# pre.net
KiCad netlist of a schematic drawn in EAGLE
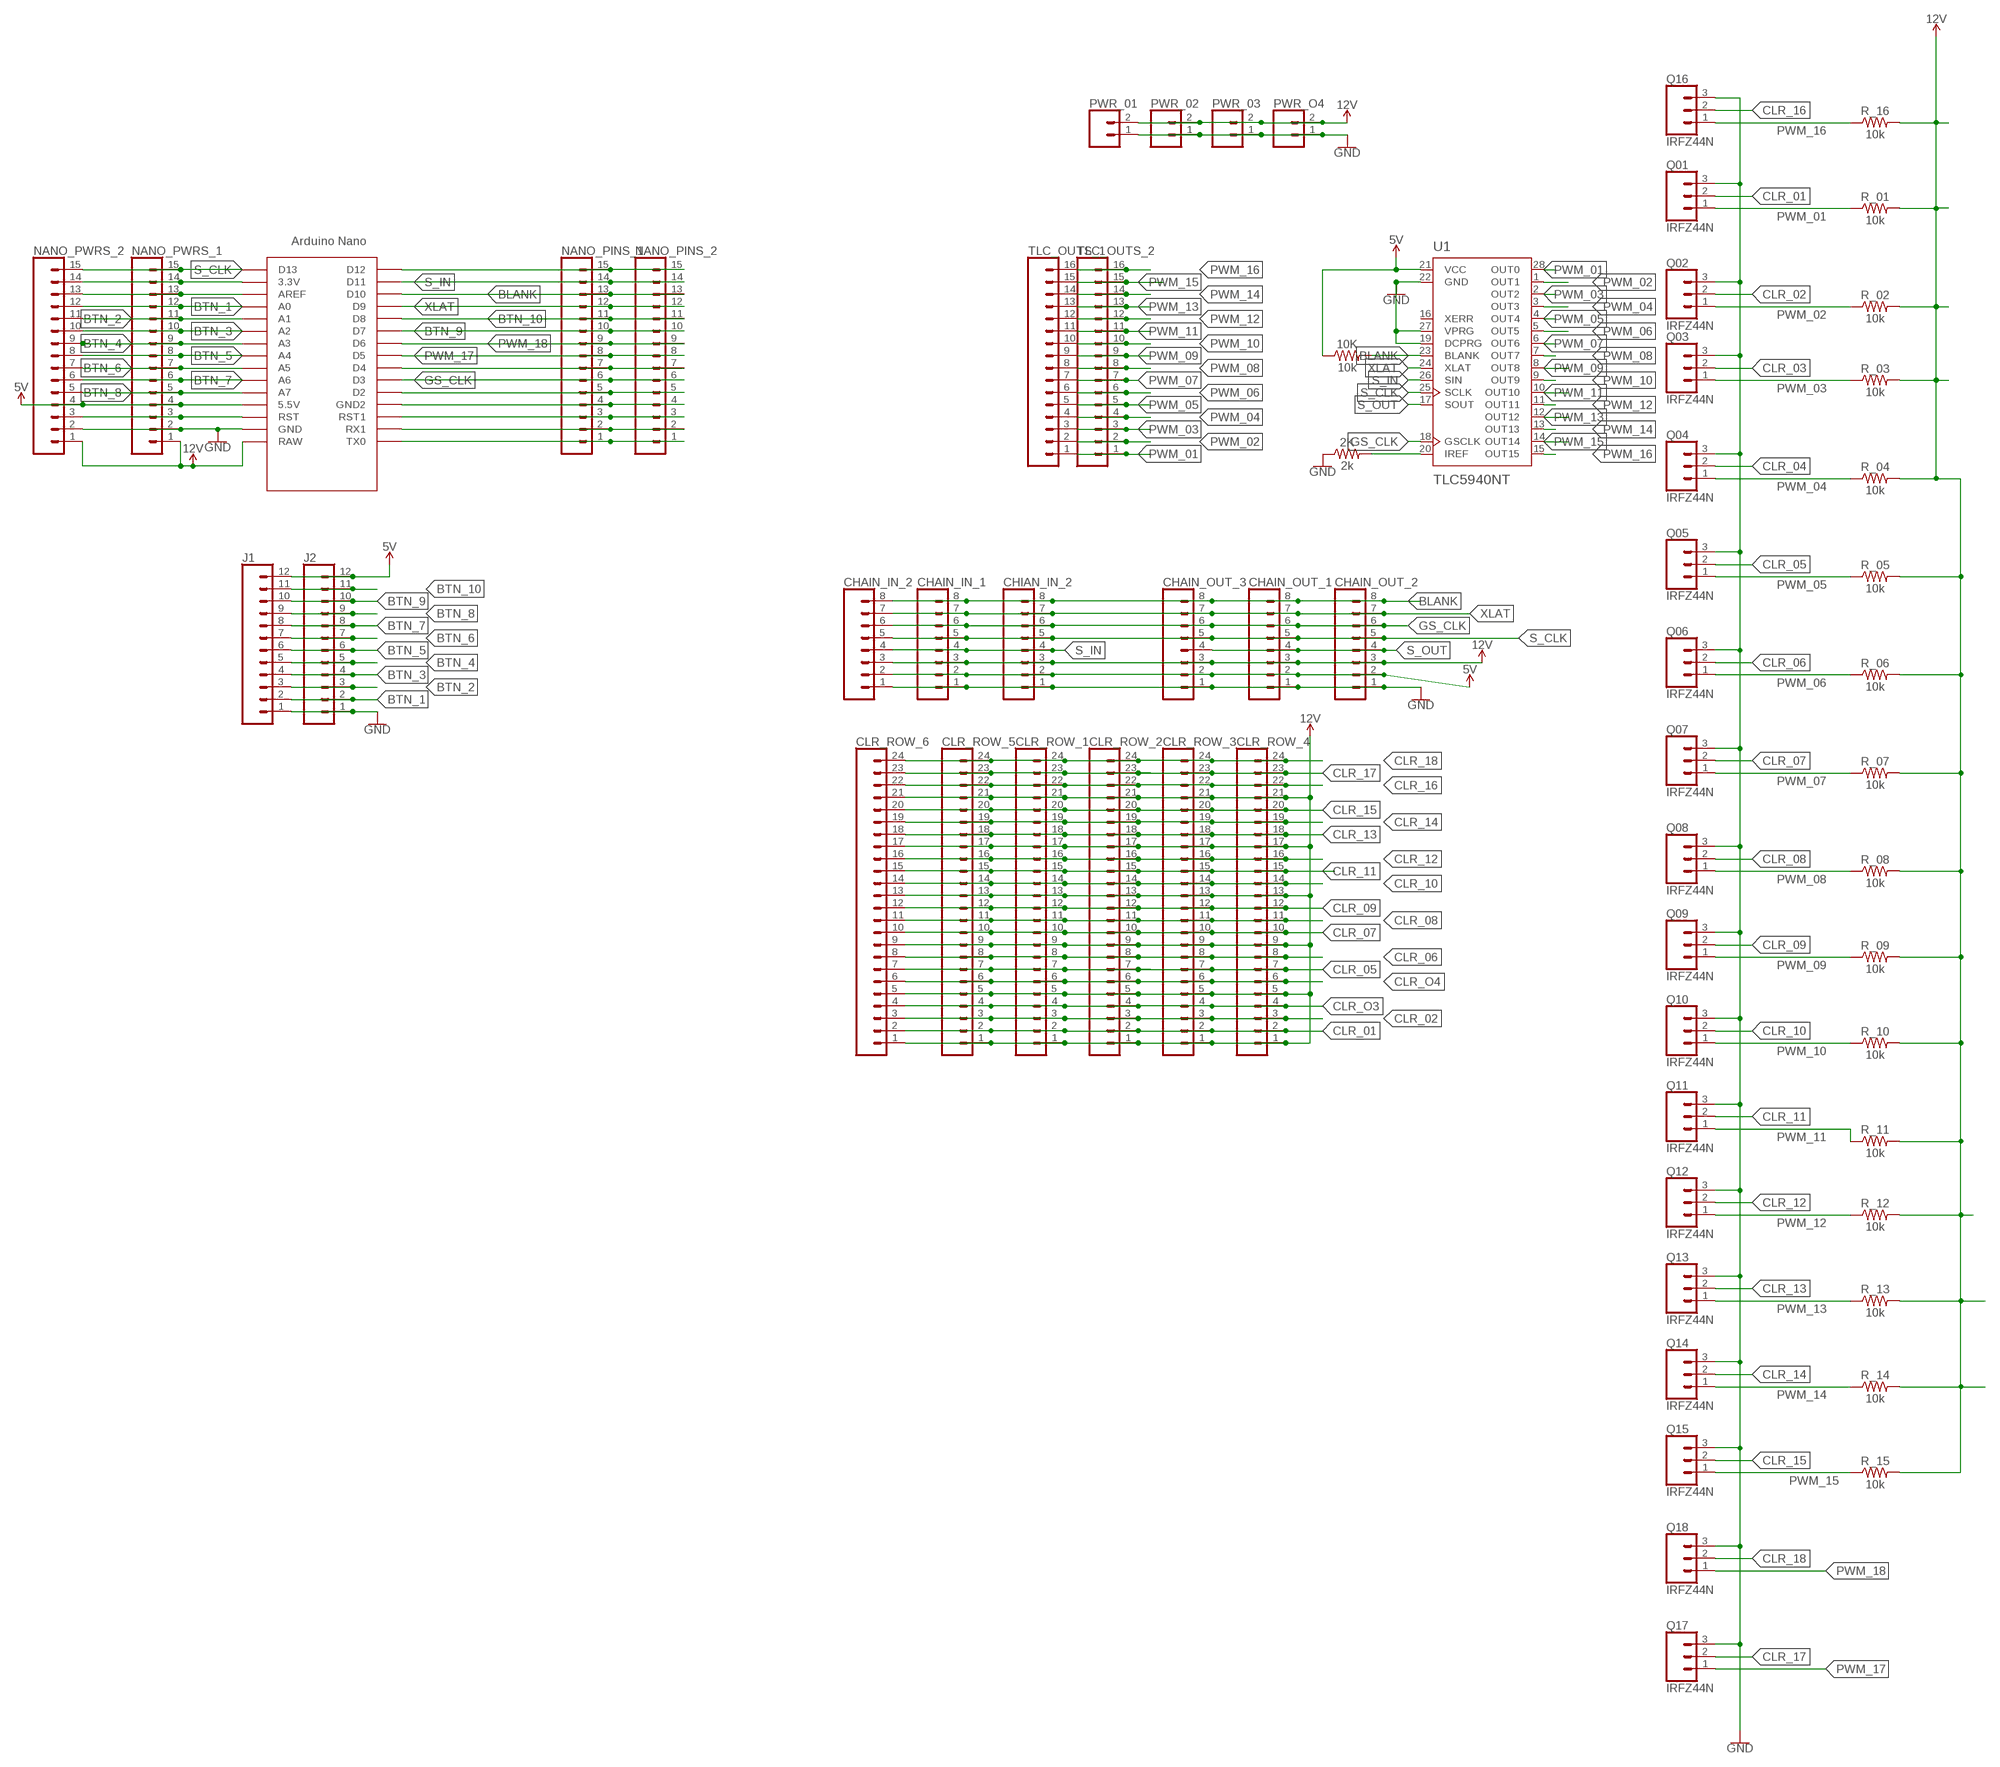
[diagram p0: schematic, sheet 1]

(export (version "E")
  (design (tool "Eeschema 10.0.6"))
  (components
    (comp (ref "2K")
      (value "2k")
      (footprint "eagle-import:AXIAL-0.3")
      (libsource (lib "eagle-import") (part "10OHM-HORIZ-1/4W-1%"))
    )
    (comp (ref "10K")
      (value "10k")
      (footprint "eagle-import:AXIAL-0.3")
      (libsource (lib "eagle-import") (part "10KOHM-HORIZ-1/4W-1%"))
    )
    (comp (ref "CHAIN_IN_1")
      (value "CONN_08\"")
      (footprint "eagle-import:1X08")
      (libsource (lib "eagle-import") (part "CONN_08{dblquote}"))
    )
    (comp (ref "CHAIN_IN_2")
      (value "CONN_08\"")
      (footprint "eagle-import:1X08")
      (libsource (lib "eagle-import") (part "CONN_08{dblquote}"))
    )
    (comp (ref "CHAIN_OUT_1")
      (value "CONN_08\"")
      (footprint "eagle-import:1X08")
      (libsource (lib "eagle-import") (part "CONN_08{dblquote}"))
    )
    (comp (ref "CHAIN_OUT_2")
      (value "CONN_08\"")
      (footprint "eagle-import:1X08")
      (libsource (lib "eagle-import") (part "CONN_08{dblquote}"))
    )
    (comp (ref "CHAIN_OUT_3")
      (value "CONN_08\"")
      (footprint "eagle-import:1X08")
      (libsource (lib "eagle-import") (part "CONN_08{dblquote}"))
    )
    (comp (ref "CHIAN_IN_2")
      (value "CONN_08\"")
      (footprint "eagle-import:1X08")
      (libsource (lib "eagle-import") (part "CONN_08{dblquote}"))
    )
    (comp (ref "CLR_ROW_1")
      (value "CONN_24")
      (footprint "eagle-import:1X24")
      (libsource (lib "eagle-import") (part "CONN_24"))
    )
    (comp (ref "CLR_ROW_2")
      (value "CONN_24")
      (footprint "eagle-import:1X24")
      (libsource (lib "eagle-import") (part "CONN_24"))
    )
    (comp (ref "CLR_ROW_3")
      (value "CONN_24")
      (footprint "eagle-import:1X24")
      (libsource (lib "eagle-import") (part "CONN_24"))
    )
    (comp (ref "CLR_ROW_4")
      (value "CONN_24")
      (footprint "eagle-import:1X24")
      (libsource (lib "eagle-import") (part "CONN_24"))
    )
    (comp (ref "CLR_ROW_5")
      (value "CONN_24")
      (footprint "eagle-import:1X24")
      (libsource (lib "eagle-import") (part "CONN_24"))
    )
    (comp (ref "CLR_ROW_6")
      (value "CONN_24")
      (footprint "eagle-import:1X24")
      (libsource (lib "eagle-import") (part "CONN_24"))
    )
    (comp (ref "J1")
      (value "CONN_12")
      (footprint "eagle-import:1X12")
      (libsource (lib "eagle-import") (part "CONN_12"))
    )
    (comp (ref "J2")
      (value "CONN_12")
      (footprint "eagle-import:1X12")
      (libsource (lib "eagle-import") (part "CONN_12"))
    )
    (comp (ref "NANO_PINS_1")
      (value "CONN_15")
      (footprint "eagle-import:1X15")
      (libsource (lib "eagle-import") (part "CONN_15"))
    )
    (comp (ref "NANO_PINS_2")
      (value "CONN_15")
      (footprint "eagle-import:1X15")
      (libsource (lib "eagle-import") (part "CONN_15"))
    )
    (comp (ref "NANO_PWRS_1")
      (value "CONN_15")
      (footprint "eagle-import:1X15")
      (libsource (lib "eagle-import") (part "CONN_15"))
    )
    (comp (ref "NANO_PWRS_2")
      (value "CONN_15")
      (footprint "eagle-import:1X15")
      (libsource (lib "eagle-import") (part "CONN_15"))
    )
    (comp (ref "PWR_01")
      (value "CONN_023.5MM")
      (footprint "eagle-import:SCREWTERMINAL-3.5MM-2")
      (libsource (lib "eagle-import") (part "CONN_023.5MM"))
    )
    (comp (ref "PWR_02")
      (value "CONN_023.5MM")
      (footprint "eagle-import:SCREWTERMINAL-3.5MM-2")
      (libsource (lib "eagle-import") (part "CONN_023.5MM"))
    )
    (comp (ref "PWR_03")
      (value "CONN_02")
      (footprint "eagle-import:1X02")
      (libsource (lib "eagle-import") (part "CONN_02"))
    )
    (comp (ref "PWR_O4")
      (value "CONN_02")
      (footprint "eagle-import:1X02")
      (libsource (lib "eagle-import") (part "CONN_02"))
    )
    (comp (ref "Q01")
      (value "IRFZ44N")
      (footprint "eagle-import:1X03")
      (libsource (lib "eagle-import") (part "CONN_03"))
    )
    (comp (ref "Q02")
      (value "IRFZ44N")
      (footprint "eagle-import:1X03")
      (libsource (lib "eagle-import") (part "CONN_03"))
    )
    (comp (ref "Q03")
      (value "IRFZ44N")
      (footprint "eagle-import:1X03")
      (libsource (lib "eagle-import") (part "CONN_03"))
    )
    (comp (ref "Q04")
      (value "IRFZ44N")
      (footprint "eagle-import:1X03")
      (libsource (lib "eagle-import") (part "CONN_03"))
    )
    (comp (ref "Q05")
      (value "IRFZ44N")
      (footprint "eagle-import:1X03")
      (libsource (lib "eagle-import") (part "CONN_03"))
    )
    (comp (ref "Q06")
      (value "IRFZ44N")
      (footprint "eagle-import:1X03")
      (libsource (lib "eagle-import") (part "CONN_03"))
    )
    (comp (ref "Q07")
      (value "IRFZ44N")
      (footprint "eagle-import:1X03")
      (libsource (lib "eagle-import") (part "CONN_03"))
    )
    (comp (ref "Q08")
      (value "IRFZ44N")
      (footprint "eagle-import:1X03")
      (libsource (lib "eagle-import") (part "CONN_03"))
    )
    (comp (ref "Q09")
      (value "IRFZ44N")
      (footprint "eagle-import:1X03")
      (libsource (lib "eagle-import") (part "CONN_03"))
    )
    (comp (ref "Q10")
      (value "IRFZ44N")
      (footprint "eagle-import:1X03")
      (libsource (lib "eagle-import") (part "CONN_03"))
    )
    (comp (ref "Q11")
      (value "IRFZ44N")
      (footprint "eagle-import:1X03")
      (libsource (lib "eagle-import") (part "CONN_03"))
    )
    (comp (ref "Q12")
      (value "IRFZ44N")
      (footprint "eagle-import:1X03")
      (libsource (lib "eagle-import") (part "CONN_03"))
    )
    (comp (ref "Q13")
      (value "IRFZ44N")
      (footprint "eagle-import:1X03")
      (libsource (lib "eagle-import") (part "CONN_03"))
    )
    (comp (ref "Q14")
      (value "IRFZ44N")
      (footprint "eagle-import:1X03")
      (libsource (lib "eagle-import") (part "CONN_03"))
    )
    (comp (ref "Q15")
      (value "IRFZ44N")
      (footprint "eagle-import:1X03")
      (libsource (lib "eagle-import") (part "CONN_03"))
    )
    (comp (ref "Q16")
      (value "IRFZ44N")
      (footprint "eagle-import:1X03")
      (libsource (lib "eagle-import") (part "CONN_03"))
    )
    (comp (ref "Q17")
      (value "IRFZ44N")
      (footprint "eagle-import:1X03")
      (libsource (lib "eagle-import") (part "CONN_03"))
    )
    (comp (ref "Q18")
      (value "IRFZ44N")
      (footprint "eagle-import:1X03")
      (libsource (lib "eagle-import") (part "CONN_03"))
    )
    (comp (ref "R_01")
      (value "10k")
      (footprint "eagle-import:AXIAL-0.3")
      (libsource (lib "eagle-import") (part "10KOHM-HORIZ-1/4W-1%"))
    )
    (comp (ref "R_02")
      (value "10k")
      (footprint "eagle-import:AXIAL-0.3")
      (libsource (lib "eagle-import") (part "10KOHM-HORIZ-1/4W-1%"))
    )
    (comp (ref "R_03")
      (value "10k")
      (footprint "eagle-import:AXIAL-0.3")
      (libsource (lib "eagle-import") (part "10KOHM-HORIZ-1/4W-1%"))
    )
    (comp (ref "R_04")
      (value "10k")
      (footprint "eagle-import:AXIAL-0.3")
      (libsource (lib "eagle-import") (part "10KOHM-HORIZ-1/4W-1%"))
    )
    (comp (ref "R_05")
      (value "10k")
      (footprint "eagle-import:AXIAL-0.3")
      (libsource (lib "eagle-import") (part "10KOHM-HORIZ-1/4W-1%"))
    )
    (comp (ref "R_06")
      (value "10k")
      (footprint "eagle-import:AXIAL-0.3")
      (libsource (lib "eagle-import") (part "10KOHM-HORIZ-1/4W-1%"))
    )
    (comp (ref "R_07")
      (value "10k")
      (footprint "eagle-import:AXIAL-0.3")
      (libsource (lib "eagle-import") (part "10KOHM-HORIZ-1/4W-1%"))
    )
    (comp (ref "R_08")
      (value "10k")
      (footprint "eagle-import:AXIAL-0.3")
      (libsource (lib "eagle-import") (part "10KOHM-HORIZ-1/4W-1%"))
    )
    (comp (ref "R_09")
      (value "10k")
      (footprint "eagle-import:AXIAL-0.3")
      (libsource (lib "eagle-import") (part "10KOHM-HORIZ-1/4W-1%"))
    )
    (comp (ref "R_10")
      (value "10k")
      (footprint "eagle-import:AXIAL-0.3")
      (libsource (lib "eagle-import") (part "10KOHM-HORIZ-1/4W-1%"))
    )
    (comp (ref "R_11")
      (value "10k")
      (footprint "eagle-import:AXIAL-0.3")
      (libsource (lib "eagle-import") (part "10KOHM-HORIZ-1/4W-1%"))
    )
    (comp (ref "R_12")
      (value "10k")
      (footprint "eagle-import:AXIAL-0.3")
      (libsource (lib "eagle-import") (part "10KOHM-HORIZ-1/4W-1%"))
    )
    (comp (ref "R_13")
      (value "10k")
      (footprint "eagle-import:AXIAL-0.3")
      (libsource (lib "eagle-import") (part "10KOHM-HORIZ-1/4W-1%"))
    )
    (comp (ref "R_14")
      (value "10k")
      (footprint "eagle-import:AXIAL-0.3")
      (libsource (lib "eagle-import") (part "10KOHM-HORIZ-1/4W-1%"))
    )
    (comp (ref "R_15")
      (value "10k")
      (footprint "eagle-import:AXIAL-0.3")
      (libsource (lib "eagle-import") (part "10KOHM-HORIZ-1/4W-1%"))
    )
    (comp (ref "R_16")
      (value "10k")
      (footprint "eagle-import:AXIAL-0.3")
      (libsource (lib "eagle-import") (part "10KOHM-HORIZ-1/4W-1%"))
    )
    (comp (ref "TLC_OUTS_1")
      (value "CONN_16")
      (footprint "eagle-import:1X16")
      (libsource (lib "eagle-import") (part "CONN_16"))
    )
    (comp (ref "TLC_OUTS_2")
      (value "CONN_16")
      (footprint "eagle-import:1X16")
      (libsource (lib "eagle-import") (part "CONN_16"))
    )
    (comp (ref "U$1")
      (value "NANO")
      (footprint "eagle-import:NANO")
      (libsource (lib "eagle-import") (part "NANO"))
    )
    (comp (ref "U1")
      (value "TLC5940NT")
      (footprint "eagle-import:DIL28-3")
      (libsource (lib "eagle-import") (part "TLC5940NT"))
    )
  )
  (nets
    (net (code "1") (name "5V") (class "Default")
      (node (ref "10K") (pin "P$1") (pinfunction "1_P$1") (pintype "passive"))
      (node (ref "CHAIN_IN_1") (pin "2") (pinfunction "2_2") (pintype "passive"))
      (node (ref "CHAIN_IN_2") (pin "2") (pinfunction "2_2") (pintype "passive"))
      (node (ref "CHAIN_OUT_1") (pin "2") (pinfunction "2_2") (pintype "passive"))
      (node (ref "CHAIN_OUT_2") (pin "2") (pinfunction "2_2") (pintype "passive"))
      (node (ref "CHAIN_OUT_3") (pin "2") (pinfunction "2_2") (pintype "passive"))
      (node (ref "CHIAN_IN_2") (pin "2") (pinfunction "2_2") (pintype "passive"))
      (node (ref "J1") (pin "12") (pinfunction "12_12") (pintype "passive"))
      (node (ref "J2") (pin "12") (pinfunction "12_12") (pintype "passive"))
      (node (ref "NANO_PWRS_1") (pin "4") (pinfunction "4_4") (pintype "passive"))
      (node (ref "NANO_PWRS_2") (pin "4") (pinfunction "4_4") (pintype "passive"))
      (node (ref "U$1") (pin "5V") (pinfunction "5.5V_5V") (pintype "bidirectional"))
      (node (ref "U1") (pin "21") (pinfunction "VCC_21") (pintype "power_in"))
    )
    (net (code "2") (name "12V") (class "Default")
      (node (ref "CHAIN_IN_1") (pin "3") (pinfunction "3_3") (pintype "passive"))
      (node (ref "CHAIN_IN_2") (pin "3") (pinfunction "3_3") (pintype "passive"))
      (node (ref "CHAIN_OUT_1") (pin "3") (pinfunction "3_3") (pintype "passive"))
      (node (ref "CHAIN_OUT_2") (pin "3") (pinfunction "3_3") (pintype "passive"))
      (node (ref "CHAIN_OUT_3") (pin "3") (pinfunction "3_3") (pintype "passive"))
      (node (ref "CHIAN_IN_2") (pin "3") (pinfunction "3_3") (pintype "passive"))
      (node (ref "CLR_ROW_1") (pin "1") (pinfunction "1_1") (pintype "passive"))
      (node (ref "CLR_ROW_1") (pin "13") (pinfunction "13_13") (pintype "passive"))
      (node (ref "CLR_ROW_1") (pin "17") (pinfunction "17_17") (pintype "passive"))
      (node (ref "CLR_ROW_1") (pin "21") (pinfunction "21_21") (pintype "passive"))
      (node (ref "CLR_ROW_1") (pin "5") (pinfunction "5_5") (pintype "passive"))
      (node (ref "CLR_ROW_1") (pin "9") (pinfunction "9_9") (pintype "passive"))
      (node (ref "CLR_ROW_2") (pin "1") (pinfunction "1_1") (pintype "passive"))
      (node (ref "CLR_ROW_2") (pin "13") (pinfunction "13_13") (pintype "passive"))
      (node (ref "CLR_ROW_2") (pin "17") (pinfunction "17_17") (pintype "passive"))
      (node (ref "CLR_ROW_2") (pin "21") (pinfunction "21_21") (pintype "passive"))
      (node (ref "CLR_ROW_2") (pin "5") (pinfunction "5_5") (pintype "passive"))
      (node (ref "CLR_ROW_2") (pin "9") (pinfunction "9_9") (pintype "passive"))
      (node (ref "CLR_ROW_3") (pin "1") (pinfunction "1_1") (pintype "passive"))
      (node (ref "CLR_ROW_3") (pin "13") (pinfunction "13_13") (pintype "passive"))
      (node (ref "CLR_ROW_3") (pin "17") (pinfunction "17_17") (pintype "passive"))
      (node (ref "CLR_ROW_3") (pin "21") (pinfunction "21_21") (pintype "passive"))
      (node (ref "CLR_ROW_3") (pin "5") (pinfunction "5_5") (pintype "passive"))
      (node (ref "CLR_ROW_3") (pin "9") (pinfunction "9_9") (pintype "passive"))
      (node (ref "CLR_ROW_4") (pin "1") (pinfunction "1_1") (pintype "passive"))
      (node (ref "CLR_ROW_4") (pin "13") (pinfunction "13_13") (pintype "passive"))
      (node (ref "CLR_ROW_4") (pin "17") (pinfunction "17_17") (pintype "passive"))
      (node (ref "CLR_ROW_4") (pin "21") (pinfunction "21_21") (pintype "passive"))
      (node (ref "CLR_ROW_4") (pin "5") (pinfunction "5_5") (pintype "passive"))
      (node (ref "CLR_ROW_4") (pin "9") (pinfunction "9_9") (pintype "passive"))
      (node (ref "CLR_ROW_5") (pin "1") (pinfunction "1_1") (pintype "passive"))
      (node (ref "CLR_ROW_5") (pin "13") (pinfunction "13_13") (pintype "passive"))
      (node (ref "CLR_ROW_5") (pin "17") (pinfunction "17_17") (pintype "passive"))
      (node (ref "CLR_ROW_5") (pin "21") (pinfunction "21_21") (pintype "passive"))
      (node (ref "CLR_ROW_5") (pin "5") (pinfunction "5_5") (pintype "passive"))
      (node (ref "CLR_ROW_5") (pin "9") (pinfunction "9_9") (pintype "passive"))
      (node (ref "CLR_ROW_6") (pin "1") (pinfunction "1_1") (pintype "passive"))
      (node (ref "CLR_ROW_6") (pin "13") (pinfunction "13_13") (pintype "passive"))
      (node (ref "CLR_ROW_6") (pin "17") (pinfunction "17_17") (pintype "passive"))
      (node (ref "CLR_ROW_6") (pin "21") (pinfunction "21_21") (pintype "passive"))
      (node (ref "CLR_ROW_6") (pin "5") (pinfunction "5_5") (pintype "passive"))
      (node (ref "CLR_ROW_6") (pin "9") (pinfunction "9_9") (pintype "passive"))
      (node (ref "NANO_PWRS_1") (pin "1") (pinfunction "1_1") (pintype "passive"))
      (node (ref "NANO_PWRS_2") (pin "1") (pinfunction "1_1") (pintype "passive"))
      (node (ref "PWR_01") (pin "2") (pinfunction "2_2") (pintype "passive"))
      (node (ref "PWR_02") (pin "2") (pinfunction "2_2") (pintype "passive"))
      (node (ref "PWR_03") (pin "2") (pinfunction "2_2") (pintype "passive"))
      (node (ref "PWR_O4") (pin "2") (pinfunction "2_2") (pintype "passive"))
      (node (ref "R_01") (pin "P$2") (pinfunction "2_P$2") (pintype "passive"))
      (node (ref "R_02") (pin "P$2") (pinfunction "2_P$2") (pintype "passive"))
      (node (ref "R_03") (pin "P$2") (pinfunction "2_P$2") (pintype "passive"))
      (node (ref "R_04") (pin "P$2") (pinfunction "2_P$2") (pintype "passive"))
      (node (ref "R_05") (pin "P$2") (pinfunction "2_P$2") (pintype "passive"))
      (node (ref "R_06") (pin "P$2") (pinfunction "2_P$2") (pintype "passive"))
      (node (ref "R_07") (pin "P$2") (pinfunction "2_P$2") (pintype "passive"))
      (node (ref "R_08") (pin "P$2") (pinfunction "2_P$2") (pintype "passive"))
      (node (ref "R_09") (pin "P$2") (pinfunction "2_P$2") (pintype "passive"))
      (node (ref "R_10") (pin "P$2") (pinfunction "2_P$2") (pintype "passive"))
      (node (ref "R_11") (pin "P$2") (pinfunction "2_P$2") (pintype "passive"))
      (node (ref "R_12") (pin "P$2") (pinfunction "2_P$2") (pintype "passive"))
      (node (ref "R_13") (pin "P$2") (pinfunction "2_P$2") (pintype "passive"))
      (node (ref "R_14") (pin "P$2") (pinfunction "2_P$2") (pintype "passive"))
      (node (ref "R_15") (pin "P$2") (pinfunction "2_P$2") (pintype "passive"))
      (node (ref "R_16") (pin "P$2") (pinfunction "2_P$2") (pintype "passive"))
      (node (ref "U$1") (pin "RAW") (pinfunction "RAW_RAW") (pintype "bidirectional"))
    )
    (net (code "3") (name "BLANK") (class "Default")
      (node (ref "10K") (pin "P$2") (pinfunction "2_P$2") (pintype "passive"))
      (node (ref "CHAIN_IN_1") (pin "8") (pinfunction "8_8") (pintype "passive"))
      (node (ref "CHAIN_IN_2") (pin "8") (pinfunction "8_8") (pintype "passive"))
      (node (ref "CHAIN_OUT_1") (pin "8") (pinfunction "8_8") (pintype "passive"))
      (node (ref "CHAIN_OUT_2") (pin "8") (pinfunction "8_8") (pintype "passive"))
      (node (ref "CHAIN_OUT_3") (pin "8") (pinfunction "8_8") (pintype "passive"))
      (node (ref "CHIAN_IN_2") (pin "8") (pinfunction "8_8") (pintype "passive"))
      (node (ref "NANO_PINS_1") (pin "13") (pinfunction "13_13") (pintype "passive"))
      (node (ref "NANO_PINS_2") (pin "13") (pinfunction "13_13") (pintype "passive"))
      (node (ref "U$1") (pin "D10") (pinfunction "D10_D10") (pintype "bidirectional"))
      (node (ref "U1") (pin "23") (pinfunction "BLANK_23") (pintype "input"))
    )
    (net (code "4") (name "BTN_1") (class "Default")
      (node (ref "J1") (pin "2") (pinfunction "2_2") (pintype "passive"))
      (node (ref "J2") (pin "2") (pinfunction "2_2") (pintype "passive"))
      (node (ref "NANO_PWRS_1") (pin "12") (pinfunction "12_12") (pintype "passive"))
      (node (ref "NANO_PWRS_2") (pin "12") (pinfunction "12_12") (pintype "passive"))
      (node (ref "U$1") (pin "A0") (pinfunction "A0_A0") (pintype "bidirectional"))
    )
    (net (code "5") (name "BTN_2") (class "Default")
      (node (ref "J1") (pin "3") (pinfunction "3_3") (pintype "passive"))
      (node (ref "J2") (pin "3") (pinfunction "3_3") (pintype "passive"))
      (node (ref "NANO_PWRS_1") (pin "11") (pinfunction "11_11") (pintype "passive"))
      (node (ref "NANO_PWRS_2") (pin "11") (pinfunction "11_11") (pintype "passive"))
      (node (ref "U$1") (pin "A1") (pinfunction "A1_A1") (pintype "bidirectional"))
    )
    (net (code "6") (name "BTN_3") (class "Default")
      (node (ref "J1") (pin "4") (pinfunction "4_4") (pintype "passive"))
      (node (ref "J2") (pin "4") (pinfunction "4_4") (pintype "passive"))
      (node (ref "NANO_PWRS_1") (pin "10") (pinfunction "10_10") (pintype "passive"))
      (node (ref "NANO_PWRS_2") (pin "10") (pinfunction "10_10") (pintype "passive"))
      (node (ref "U$1") (pin "A2") (pinfunction "A2_A2") (pintype "bidirectional"))
    )
    (net (code "7") (name "BTN_4") (class "Default")
      (node (ref "J1") (pin "5") (pinfunction "5_5") (pintype "passive"))
      (node (ref "J2") (pin "5") (pinfunction "5_5") (pintype "passive"))
      (node (ref "NANO_PWRS_1") (pin "9") (pinfunction "9_9") (pintype "passive"))
      (node (ref "NANO_PWRS_2") (pin "9") (pinfunction "9_9") (pintype "passive"))
      (node (ref "U$1") (pin "A3") (pinfunction "A3_A3") (pintype "bidirectional"))
    )
    (net (code "8") (name "BTN_5") (class "Default")
      (node (ref "J1") (pin "6") (pinfunction "6_6") (pintype "passive"))
      (node (ref "J2") (pin "6") (pinfunction "6_6") (pintype "passive"))
      (node (ref "NANO_PWRS_1") (pin "8") (pinfunction "8_8") (pintype "passive"))
      (node (ref "NANO_PWRS_2") (pin "8") (pinfunction "8_8") (pintype "passive"))
      (node (ref "U$1") (pin "A4") (pinfunction "A4_A4") (pintype "bidirectional"))
    )
    (net (code "9") (name "BTN_6") (class "Default")
      (node (ref "J1") (pin "7") (pinfunction "7_7") (pintype "passive"))
      (node (ref "J2") (pin "7") (pinfunction "7_7") (pintype "passive"))
      (node (ref "NANO_PWRS_1") (pin "7") (pinfunction "7_7") (pintype "passive"))
      (node (ref "NANO_PWRS_2") (pin "7") (pinfunction "7_7") (pintype "passive"))
      (node (ref "U$1") (pin "A5") (pinfunction "A5_A5") (pintype "bidirectional"))
    )
    (net (code "10") (name "BTN_7") (class "Default")
      (node (ref "J1") (pin "8") (pinfunction "8_8") (pintype "passive"))
      (node (ref "J2") (pin "8") (pinfunction "8_8") (pintype "passive"))
      (node (ref "NANO_PWRS_1") (pin "6") (pinfunction "6_6") (pintype "passive"))
      (node (ref "NANO_PWRS_2") (pin "6") (pinfunction "6_6") (pintype "passive"))
      (node (ref "U$1") (pin "A6") (pinfunction "A6_A6") (pintype "bidirectional"))
    )
    (net (code "11") (name "BTN_8") (class "Default")
      (node (ref "J1") (pin "9") (pinfunction "9_9") (pintype "passive"))
      (node (ref "J2") (pin "9") (pinfunction "9_9") (pintype "passive"))
      (node (ref "NANO_PWRS_1") (pin "5") (pinfunction "5_5") (pintype "passive"))
      (node (ref "NANO_PWRS_2") (pin "5") (pinfunction "5_5") (pintype "passive"))
      (node (ref "U$1") (pin "A7") (pinfunction "A7_A7") (pintype "bidirectional"))
    )
    (net (code "12") (name "BTN_9") (class "Default")
      (node (ref "J1") (pin "10") (pinfunction "10_10") (pintype "passive"))
      (node (ref "J2") (pin "10") (pinfunction "10_10") (pintype "passive"))
      (node (ref "NANO_PINS_1") (pin "10") (pinfunction "10_10") (pintype "passive"))
      (node (ref "NANO_PINS_2") (pin "10") (pinfunction "10_10") (pintype "passive"))
      (node (ref "U$1") (pin "D7") (pinfunction "D7_D7") (pintype "bidirectional"))
    )
    (net (code "13") (name "BTN_10") (class "Default")
      (node (ref "J1") (pin "11") (pinfunction "11_11") (pintype "passive"))
      (node (ref "J2") (pin "11") (pinfunction "11_11") (pintype "passive"))
      (node (ref "NANO_PINS_1") (pin "11") (pinfunction "11_11") (pintype "passive"))
      (node (ref "NANO_PINS_2") (pin "11") (pinfunction "11_11") (pintype "passive"))
      (node (ref "U$1") (pin "D8") (pinfunction "D8_D8") (pintype "bidirectional"))
    )
    (net (code "14") (name "CLR_01") (class "Default")
      (node (ref "CLR_ROW_1") (pin "2") (pinfunction "2_2") (pintype "passive"))
      (node (ref "CLR_ROW_2") (pin "2") (pinfunction "2_2") (pintype "passive"))
      (node (ref "CLR_ROW_3") (pin "2") (pinfunction "2_2") (pintype "passive"))
      (node (ref "CLR_ROW_4") (pin "2") (pinfunction "2_2") (pintype "passive"))
      (node (ref "CLR_ROW_5") (pin "2") (pinfunction "2_2") (pintype "passive"))
      (node (ref "CLR_ROW_6") (pin "2") (pinfunction "2_2") (pintype "passive"))
      (node (ref "Q01") (pin "2") (pinfunction "2_2") (pintype "passive"))
    )
    (net (code "15") (name "CLR_02") (class "Default")
      (node (ref "CLR_ROW_1") (pin "3") (pinfunction "3_3") (pintype "passive"))
      (node (ref "CLR_ROW_2") (pin "3") (pinfunction "3_3") (pintype "passive"))
      (node (ref "CLR_ROW_3") (pin "3") (pinfunction "3_3") (pintype "passive"))
      (node (ref "CLR_ROW_4") (pin "3") (pinfunction "3_3") (pintype "passive"))
      (node (ref "CLR_ROW_5") (pin "3") (pinfunction "3_3") (pintype "passive"))
      (node (ref "CLR_ROW_6") (pin "3") (pinfunction "3_3") (pintype "passive"))
      (node (ref "Q02") (pin "2") (pinfunction "2_2") (pintype "passive"))
    )
    (net (code "16") (name "CLR_03") (class "Default")
      (node (ref "Q03") (pin "2") (pinfunction "2_2") (pintype "passive"))
    )
    (net (code "17") (name "CLR_04") (class "Default")
      (node (ref "Q04") (pin "2") (pinfunction "2_2") (pintype "passive"))
    )
    (net (code "18") (name "CLR_05") (class "Default")
      (node (ref "CLR_ROW_1") (pin "7") (pinfunction "7_7") (pintype "passive"))
      (node (ref "CLR_ROW_2") (pin "7") (pinfunction "7_7") (pintype "passive"))
      (node (ref "CLR_ROW_3") (pin "7") (pinfunction "7_7") (pintype "passive"))
      (node (ref "CLR_ROW_4") (pin "7") (pinfunction "7_7") (pintype "passive"))
      (node (ref "CLR_ROW_5") (pin "7") (pinfunction "7_7") (pintype "passive"))
      (node (ref "CLR_ROW_6") (pin "7") (pinfunction "7_7") (pintype "passive"))
      (node (ref "Q05") (pin "2") (pinfunction "2_2") (pintype "passive"))
    )
    (net (code "19") (name "CLR_06") (class "Default")
      (node (ref "CLR_ROW_1") (pin "8") (pinfunction "8_8") (pintype "passive"))
      (node (ref "CLR_ROW_2") (pin "8") (pinfunction "8_8") (pintype "passive"))
      (node (ref "CLR_ROW_3") (pin "8") (pinfunction "8_8") (pintype "passive"))
      (node (ref "CLR_ROW_4") (pin "8") (pinfunction "8_8") (pintype "passive"))
      (node (ref "CLR_ROW_5") (pin "8") (pinfunction "8_8") (pintype "passive"))
      (node (ref "CLR_ROW_6") (pin "8") (pinfunction "8_8") (pintype "passive"))
      (node (ref "Q06") (pin "2") (pinfunction "2_2") (pintype "passive"))
    )
    (net (code "20") (name "CLR_07") (class "Default")
      (node (ref "CLR_ROW_1") (pin "10") (pinfunction "10_10") (pintype "passive"))
      (node (ref "CLR_ROW_2") (pin "10") (pinfunction "10_10") (pintype "passive"))
      (node (ref "CLR_ROW_3") (pin "10") (pinfunction "10_10") (pintype "passive"))
      (node (ref "CLR_ROW_4") (pin "10") (pinfunction "10_10") (pintype "passive"))
      (node (ref "CLR_ROW_5") (pin "10") (pinfunction "10_10") (pintype "passive"))
      (node (ref "CLR_ROW_6") (pin "10") (pinfunction "10_10") (pintype "passive"))
      (node (ref "Q07") (pin "2") (pinfunction "2_2") (pintype "passive"))
    )
    (net (code "21") (name "CLR_08") (class "Default")
      (node (ref "CLR_ROW_1") (pin "11") (pinfunction "11_11") (pintype "passive"))
      (node (ref "CLR_ROW_2") (pin "11") (pinfunction "11_11") (pintype "passive"))
      (node (ref "CLR_ROW_3") (pin "11") (pinfunction "11_11") (pintype "passive"))
      (node (ref "CLR_ROW_4") (pin "11") (pinfunction "11_11") (pintype "passive"))
      (node (ref "CLR_ROW_5") (pin "11") (pinfunction "11_11") (pintype "passive"))
      (node (ref "CLR_ROW_6") (pin "11") (pinfunction "11_11") (pintype "passive"))
      (node (ref "Q08") (pin "2") (pinfunction "2_2") (pintype "passive"))
    )
    (net (code "22") (name "CLR_09") (class "Default")
      (node (ref "CLR_ROW_1") (pin "12") (pinfunction "12_12") (pintype "passive"))
      (node (ref "CLR_ROW_2") (pin "12") (pinfunction "12_12") (pintype "passive"))
      (node (ref "CLR_ROW_3") (pin "12") (pinfunction "12_12") (pintype "passive"))
      (node (ref "CLR_ROW_4") (pin "12") (pinfunction "12_12") (pintype "passive"))
      (node (ref "CLR_ROW_5") (pin "12") (pinfunction "12_12") (pintype "passive"))
      (node (ref "CLR_ROW_6") (pin "12") (pinfunction "12_12") (pintype "passive"))
      (node (ref "Q09") (pin "2") (pinfunction "2_2") (pintype "passive"))
    )
    (net (code "23") (name "CLR_10") (class "Default")
      (node (ref "CLR_ROW_1") (pin "14") (pinfunction "14_14") (pintype "passive"))
      (node (ref "CLR_ROW_2") (pin "14") (pinfunction "14_14") (pintype "passive"))
      (node (ref "CLR_ROW_3") (pin "14") (pinfunction "14_14") (pintype "passive"))
      (node (ref "CLR_ROW_4") (pin "14") (pinfunction "14_14") (pintype "passive"))
      (node (ref "CLR_ROW_5") (pin "14") (pinfunction "14_14") (pintype "passive"))
      (node (ref "CLR_ROW_6") (pin "14") (pinfunction "14_14") (pintype "passive"))
      (node (ref "Q10") (pin "2") (pinfunction "2_2") (pintype "passive"))
    )
    (net (code "24") (name "CLR_11") (class "Default")
      (node (ref "CLR_ROW_1") (pin "15") (pinfunction "15_15") (pintype "passive"))
      (node (ref "CLR_ROW_2") (pin "15") (pinfunction "15_15") (pintype "passive"))
      (node (ref "CLR_ROW_3") (pin "15") (pinfunction "15_15") (pintype "passive"))
      (node (ref "CLR_ROW_4") (pin "15") (pinfunction "15_15") (pintype "passive"))
      (node (ref "CLR_ROW_5") (pin "15") (pinfunction "15_15") (pintype "passive"))
      (node (ref "CLR_ROW_6") (pin "15") (pinfunction "15_15") (pintype "passive"))
      (node (ref "Q11") (pin "2") (pinfunction "2_2") (pintype "passive"))
    )
    (net (code "25") (name "CLR_12") (class "Default")
      (node (ref "CLR_ROW_1") (pin "16") (pinfunction "16_16") (pintype "passive"))
      (node (ref "CLR_ROW_2") (pin "16") (pinfunction "16_16") (pintype "passive"))
      (node (ref "CLR_ROW_3") (pin "16") (pinfunction "16_16") (pintype "passive"))
      (node (ref "CLR_ROW_4") (pin "16") (pinfunction "16_16") (pintype "passive"))
      (node (ref "CLR_ROW_5") (pin "16") (pinfunction "16_16") (pintype "passive"))
      (node (ref "CLR_ROW_6") (pin "16") (pinfunction "16_16") (pintype "passive"))
      (node (ref "Q12") (pin "2") (pinfunction "2_2") (pintype "passive"))
    )
    (net (code "26") (name "CLR_13") (class "Default")
      (node (ref "CLR_ROW_1") (pin "18") (pinfunction "18_18") (pintype "passive"))
      (node (ref "CLR_ROW_2") (pin "18") (pinfunction "18_18") (pintype "passive"))
      (node (ref "CLR_ROW_3") (pin "18") (pinfunction "18_18") (pintype "passive"))
      (node (ref "CLR_ROW_4") (pin "18") (pinfunction "18_18") (pintype "passive"))
      (node (ref "CLR_ROW_5") (pin "18") (pinfunction "18_18") (pintype "passive"))
      (node (ref "CLR_ROW_6") (pin "18") (pinfunction "18_18") (pintype "passive"))
      (node (ref "Q13") (pin "2") (pinfunction "2_2") (pintype "passive"))
    )
    (net (code "27") (name "CLR_14") (class "Default")
      (node (ref "CLR_ROW_1") (pin "19") (pinfunction "19_19") (pintype "passive"))
      (node (ref "CLR_ROW_2") (pin "19") (pinfunction "19_19") (pintype "passive"))
      (node (ref "CLR_ROW_3") (pin "19") (pinfunction "19_19") (pintype "passive"))
      (node (ref "CLR_ROW_4") (pin "19") (pinfunction "19_19") (pintype "passive"))
      (node (ref "CLR_ROW_5") (pin "19") (pinfunction "19_19") (pintype "passive"))
      (node (ref "CLR_ROW_6") (pin "19") (pinfunction "19_19") (pintype "passive"))
      (node (ref "Q14") (pin "2") (pinfunction "2_2") (pintype "passive"))
    )
    (net (code "28") (name "CLR_15") (class "Default")
      (node (ref "CLR_ROW_1") (pin "20") (pinfunction "20_20") (pintype "passive"))
      (node (ref "CLR_ROW_2") (pin "20") (pinfunction "20_20") (pintype "passive"))
      (node (ref "CLR_ROW_3") (pin "20") (pinfunction "20_20") (pintype "passive"))
      (node (ref "CLR_ROW_4") (pin "20") (pinfunction "20_20") (pintype "passive"))
      (node (ref "CLR_ROW_5") (pin "20") (pinfunction "20_20") (pintype "passive"))
      (node (ref "CLR_ROW_6") (pin "20") (pinfunction "20_20") (pintype "passive"))
      (node (ref "Q15") (pin "2") (pinfunction "2_2") (pintype "passive"))
    )
    (net (code "29") (name "CLR_16") (class "Default")
      (node (ref "CLR_ROW_1") (pin "22") (pinfunction "22_22") (pintype "passive"))
      (node (ref "CLR_ROW_2") (pin "22") (pinfunction "22_22") (pintype "passive"))
      (node (ref "CLR_ROW_3") (pin "22") (pinfunction "22_22") (pintype "passive"))
      (node (ref "CLR_ROW_4") (pin "22") (pinfunction "22_22") (pintype "passive"))
      (node (ref "CLR_ROW_5") (pin "22") (pinfunction "22_22") (pintype "passive"))
      (node (ref "CLR_ROW_6") (pin "22") (pinfunction "22_22") (pintype "passive"))
      (node (ref "Q16") (pin "2") (pinfunction "2_2") (pintype "passive"))
    )
    (net (code "30") (name "CLR_17") (class "Default")
      (node (ref "CLR_ROW_1") (pin "23") (pinfunction "23_23") (pintype "passive"))
      (node (ref "CLR_ROW_2") (pin "23") (pinfunction "23_23") (pintype "passive"))
      (node (ref "CLR_ROW_3") (pin "23") (pinfunction "23_23") (pintype "passive"))
      (node (ref "CLR_ROW_4") (pin "23") (pinfunction "23_23") (pintype "passive"))
      (node (ref "CLR_ROW_5") (pin "23") (pinfunction "23_23") (pintype "passive"))
      (node (ref "CLR_ROW_6") (pin "23") (pinfunction "23_23") (pintype "passive"))
      (node (ref "Q17") (pin "2") (pinfunction "2_2") (pintype "passive"))
    )
    (net (code "31") (name "CLR_18") (class "Default")
      (node (ref "CLR_ROW_1") (pin "24") (pinfunction "24_24") (pintype "passive"))
      (node (ref "CLR_ROW_2") (pin "24") (pinfunction "24_24") (pintype "passive"))
      (node (ref "CLR_ROW_3") (pin "24") (pinfunction "24_24") (pintype "passive"))
      (node (ref "CLR_ROW_4") (pin "24") (pinfunction "24_24") (pintype "passive"))
      (node (ref "CLR_ROW_5") (pin "24") (pinfunction "24_24") (pintype "passive"))
      (node (ref "CLR_ROW_6") (pin "24") (pinfunction "24_24") (pintype "passive"))
      (node (ref "Q18") (pin "2") (pinfunction "2_2") (pintype "passive"))
    )
    (net (code "32") (name "CLR_O3") (class "Default")
      (node (ref "CLR_ROW_1") (pin "4") (pinfunction "4_4") (pintype "passive"))
      (node (ref "CLR_ROW_2") (pin "4") (pinfunction "4_4") (pintype "passive"))
      (node (ref "CLR_ROW_3") (pin "4") (pinfunction "4_4") (pintype "passive"))
      (node (ref "CLR_ROW_4") (pin "4") (pinfunction "4_4") (pintype "passive"))
      (node (ref "CLR_ROW_5") (pin "4") (pinfunction "4_4") (pintype "passive"))
      (node (ref "CLR_ROW_6") (pin "4") (pinfunction "4_4") (pintype "passive"))
    )
    (net (code "33") (name "CLR_O4") (class "Default")
      (node (ref "CLR_ROW_1") (pin "6") (pinfunction "6_6") (pintype "passive"))
      (node (ref "CLR_ROW_2") (pin "6") (pinfunction "6_6") (pintype "passive"))
      (node (ref "CLR_ROW_3") (pin "6") (pinfunction "6_6") (pintype "passive"))
      (node (ref "CLR_ROW_4") (pin "6") (pinfunction "6_6") (pintype "passive"))
      (node (ref "CLR_ROW_5") (pin "6") (pinfunction "6_6") (pintype "passive"))
      (node (ref "CLR_ROW_6") (pin "6") (pinfunction "6_6") (pintype "passive"))
    )
    (net (code "34") (name "GND") (class "Default")
      (node (ref "2K") (pin "P$1") (pinfunction "1_P$1") (pintype "passive"))
      (node (ref "CHAIN_IN_1") (pin "1") (pinfunction "1_1") (pintype "passive"))
      (node (ref "CHAIN_IN_2") (pin "1") (pinfunction "1_1") (pintype "passive"))
      (node (ref "CHAIN_OUT_1") (pin "1") (pinfunction "1_1") (pintype "passive"))
      (node (ref "CHAIN_OUT_2") (pin "1") (pinfunction "1_1") (pintype "passive"))
      (node (ref "CHAIN_OUT_3") (pin "1") (pinfunction "1_1") (pintype "passive"))
      (node (ref "CHIAN_IN_2") (pin "1") (pinfunction "1_1") (pintype "passive"))
      (node (ref "J1") (pin "1") (pinfunction "1_1") (pintype "passive"))
      (node (ref "J2") (pin "1") (pinfunction "1_1") (pintype "passive"))
      (node (ref "NANO_PINS_1") (pin "4") (pinfunction "4_4") (pintype "passive"))
      (node (ref "NANO_PINS_2") (pin "4") (pinfunction "4_4") (pintype "passive"))
      (node (ref "NANO_PWRS_1") (pin "2") (pinfunction "2_2") (pintype "passive"))
      (node (ref "NANO_PWRS_2") (pin "2") (pinfunction "2_2") (pintype "passive"))
      (node (ref "PWR_01") (pin "1") (pinfunction "1_1") (pintype "passive"))
      (node (ref "PWR_02") (pin "1") (pinfunction "1_1") (pintype "passive"))
      (node (ref "PWR_03") (pin "1") (pinfunction "1_1") (pintype "passive"))
      (node (ref "PWR_O4") (pin "1") (pinfunction "1_1") (pintype "passive"))
      (node (ref "Q01") (pin "3") (pinfunction "3_3") (pintype "passive"))
      (node (ref "Q02") (pin "3") (pinfunction "3_3") (pintype "passive"))
      (node (ref "Q03") (pin "3") (pinfunction "3_3") (pintype "passive"))
      (node (ref "Q04") (pin "3") (pinfunction "3_3") (pintype "passive"))
      (node (ref "Q05") (pin "3") (pinfunction "3_3") (pintype "passive"))
      (node (ref "Q06") (pin "3") (pinfunction "3_3") (pintype "passive"))
      (node (ref "Q07") (pin "3") (pinfunction "3_3") (pintype "passive"))
      (node (ref "Q08") (pin "3") (pinfunction "3_3") (pintype "passive"))
      (node (ref "Q09") (pin "3") (pinfunction "3_3") (pintype "passive"))
      (node (ref "Q10") (pin "3") (pinfunction "3_3") (pintype "passive"))
      (node (ref "Q11") (pin "3") (pinfunction "3_3") (pintype "passive"))
      (node (ref "Q12") (pin "3") (pinfunction "3_3") (pintype "passive"))
      (node (ref "Q13") (pin "3") (pinfunction "3_3") (pintype "passive"))
      (node (ref "Q14") (pin "3") (pinfunction "3_3") (pintype "passive"))
      (node (ref "Q15") (pin "3") (pinfunction "3_3") (pintype "passive"))
      (node (ref "Q16") (pin "3") (pinfunction "3_3") (pintype "passive"))
      (node (ref "Q17") (pin "3") (pinfunction "3_3") (pintype "passive"))
      (node (ref "Q18") (pin "3") (pinfunction "3_3") (pintype "passive"))
      (node (ref "U$1") (pin "GND") (pinfunction "GND_GND") (pintype "bidirectional"))
      (node (ref "U$1") (pin "GND1") (pinfunction "GND2_GND1") (pintype "bidirectional"))
      (node (ref "U1") (pin "19") (pinfunction "DCPRG_19") (pintype "input"))
      (node (ref "U1") (pin "22") (pinfunction "GND_22") (pintype "power_in"))
      (node (ref "U1") (pin "27") (pinfunction "VPRG_27") (pintype "input"))
    )
    (net (code "35") (name "GS_CLK") (class "Default")
      (node (ref "CHAIN_IN_1") (pin "6") (pinfunction "6_6") (pintype "passive"))
      (node (ref "CHAIN_IN_2") (pin "6") (pinfunction "6_6") (pintype "passive"))
      (node (ref "CHAIN_OUT_1") (pin "6") (pinfunction "6_6") (pintype "passive"))
      (node (ref "CHAIN_OUT_2") (pin "6") (pinfunction "6_6") (pintype "passive"))
      (node (ref "CHAIN_OUT_3") (pin "6") (pinfunction "6_6") (pintype "passive"))
      (node (ref "CHIAN_IN_2") (pin "6") (pinfunction "6_6") (pintype "passive"))
      (node (ref "NANO_PINS_1") (pin "6") (pinfunction "6_6") (pintype "passive"))
      (node (ref "NANO_PINS_2") (pin "6") (pinfunction "6_6") (pintype "passive"))
      (node (ref "U$1") (pin "D3") (pinfunction "D3_D3") (pintype "bidirectional"))
      (node (ref "U1") (pin "18") (pinfunction "GSCLK_18") (pintype "input"))
    )
    (net (code "36") (name "Net-(2K-2)") (class "Default")
      (node (ref "2K") (pin "P$2") (pinfunction "2_P$2") (pintype "passive"))
      (node (ref "U1") (pin "20") (pinfunction "IREF_20") (pintype "passive"))
    )
    (net (code "37") (name "Net-(NANO_PINS_1-Pad1)") (class "Default")
      (node (ref "NANO_PINS_1") (pin "1") (pinfunction "1_1") (pintype "passive"))
      (node (ref "NANO_PINS_2") (pin "1") (pinfunction "1_1") (pintype "passive"))
      (node (ref "U$1") (pin "TX0") (pinfunction "TX0_TX0") (pintype "bidirectional"))
    )
    (net (code "38") (name "Net-(NANO_PINS_1-Pad2)") (class "Default")
      (node (ref "NANO_PINS_1") (pin "2") (pinfunction "2_2") (pintype "passive"))
      (node (ref "NANO_PINS_2") (pin "2") (pinfunction "2_2") (pintype "passive"))
      (node (ref "U$1") (pin "RX1") (pinfunction "RX1_RX1") (pintype "bidirectional"))
    )
    (net (code "39") (name "Net-(NANO_PINS_1-Pad3)") (class "Default")
      (node (ref "NANO_PINS_1") (pin "3") (pinfunction "3_3") (pintype "passive"))
      (node (ref "NANO_PINS_2") (pin "3") (pinfunction "3_3") (pintype "passive"))
      (node (ref "U$1") (pin "RST1") (pinfunction "RST1_RST1") (pintype "bidirectional"))
    )
    (net (code "40") (name "Net-(NANO_PINS_1-Pad5)") (class "Default")
      (node (ref "NANO_PINS_1") (pin "5") (pinfunction "5_5") (pintype "passive"))
      (node (ref "NANO_PINS_2") (pin "5") (pinfunction "5_5") (pintype "passive"))
      (node (ref "U$1") (pin "D2") (pinfunction "D2_D2") (pintype "bidirectional"))
    )
    (net (code "41") (name "Net-(NANO_PINS_1-Pad7)") (class "Default")
      (node (ref "NANO_PINS_1") (pin "7") (pinfunction "7_7") (pintype "passive"))
      (node (ref "NANO_PINS_2") (pin "7") (pinfunction "7_7") (pintype "passive"))
      (node (ref "U$1") (pin "D4") (pinfunction "D4_D4") (pintype "bidirectional"))
    )
    (net (code "42") (name "Net-(NANO_PINS_1-Pad15)") (class "Default")
      (node (ref "NANO_PINS_1") (pin "15") (pinfunction "15_15") (pintype "passive"))
      (node (ref "NANO_PINS_2") (pin "15") (pinfunction "15_15") (pintype "passive"))
      (node (ref "U$1") (pin "D12") (pinfunction "D12_D12") (pintype "bidirectional"))
    )
    (net (code "43") (name "Net-(NANO_PWRS_1-Pad3)") (class "Default")
      (node (ref "NANO_PWRS_1") (pin "3") (pinfunction "3_3") (pintype "passive"))
      (node (ref "NANO_PWRS_2") (pin "3") (pinfunction "3_3") (pintype "passive"))
      (node (ref "U$1") (pin "RST") (pinfunction "RST_RST") (pintype "bidirectional"))
    )
    (net (code "44") (name "Net-(NANO_PWRS_1-Pad13)") (class "Default")
      (node (ref "NANO_PWRS_1") (pin "13") (pinfunction "13_13") (pintype "passive"))
      (node (ref "NANO_PWRS_2") (pin "13") (pinfunction "13_13") (pintype "passive"))
      (node (ref "U$1") (pin "AREF") (pinfunction "AREF_AREF") (pintype "bidirectional"))
    )
    (net (code "45") (name "Net-(NANO_PWRS_1-Pad14)") (class "Default")
      (node (ref "NANO_PWRS_1") (pin "14") (pinfunction "14_14") (pintype "passive"))
      (node (ref "NANO_PWRS_2") (pin "14") (pinfunction "14_14") (pintype "passive"))
      (node (ref "U$1") (pin "3.3V") (pinfunction "3.3V_3.3V") (pintype "bidirectional"))
    )
    (net (code "46") (name "PWM_01") (class "Default")
      (node (ref "Q01") (pin "1") (pinfunction "1_1") (pintype "passive"))
      (node (ref "R_01") (pin "P$1") (pinfunction "1_P$1") (pintype "passive"))
      (node (ref "TLC_OUTS_1") (pin "1") (pinfunction "1_1") (pintype "passive"))
      (node (ref "TLC_OUTS_2") (pin "1") (pinfunction "1_1") (pintype "passive"))
      (node (ref "U1") (pin "28") (pinfunction "OUT0_28") (pintype "output"))
    )
    (net (code "47") (name "PWM_02") (class "Default")
      (node (ref "Q02") (pin "1") (pinfunction "1_1") (pintype "passive"))
      (node (ref "R_02") (pin "P$1") (pinfunction "1_P$1") (pintype "passive"))
      (node (ref "TLC_OUTS_1") (pin "2") (pinfunction "2_2") (pintype "passive"))
      (node (ref "TLC_OUTS_2") (pin "2") (pinfunction "2_2") (pintype "passive"))
      (node (ref "U1") (pin "1") (pinfunction "OUT1_1") (pintype "output"))
    )
    (net (code "48") (name "PWM_03") (class "Default")
      (node (ref "Q03") (pin "1") (pinfunction "1_1") (pintype "passive"))
      (node (ref "R_03") (pin "P$1") (pinfunction "1_P$1") (pintype "passive"))
      (node (ref "TLC_OUTS_1") (pin "3") (pinfunction "3_3") (pintype "passive"))
      (node (ref "TLC_OUTS_2") (pin "3") (pinfunction "3_3") (pintype "passive"))
      (node (ref "U1") (pin "2") (pinfunction "OUT2_2") (pintype "output"))
    )
    (net (code "49") (name "PWM_04") (class "Default")
      (node (ref "Q04") (pin "1") (pinfunction "1_1") (pintype "passive"))
      (node (ref "R_04") (pin "P$1") (pinfunction "1_P$1") (pintype "passive"))
      (node (ref "TLC_OUTS_1") (pin "4") (pinfunction "4_4") (pintype "passive"))
      (node (ref "TLC_OUTS_2") (pin "4") (pinfunction "4_4") (pintype "passive"))
      (node (ref "U1") (pin "3") (pinfunction "OUT3_3") (pintype "output"))
    )
    (net (code "50") (name "PWM_05") (class "Default")
      (node (ref "Q05") (pin "1") (pinfunction "1_1") (pintype "passive"))
      (node (ref "R_05") (pin "P$1") (pinfunction "1_P$1") (pintype "passive"))
      (node (ref "TLC_OUTS_1") (pin "5") (pinfunction "5_5") (pintype "passive"))
      (node (ref "TLC_OUTS_2") (pin "5") (pinfunction "5_5") (pintype "passive"))
      (node (ref "U1") (pin "4") (pinfunction "OUT4_4") (pintype "output"))
    )
    (net (code "51") (name "PWM_06") (class "Default")
      (node (ref "Q06") (pin "1") (pinfunction "1_1") (pintype "passive"))
      (node (ref "R_06") (pin "P$1") (pinfunction "1_P$1") (pintype "passive"))
      (node (ref "TLC_OUTS_1") (pin "6") (pinfunction "6_6") (pintype "passive"))
      (node (ref "TLC_OUTS_2") (pin "6") (pinfunction "6_6") (pintype "passive"))
      (node (ref "U1") (pin "5") (pinfunction "OUT5_5") (pintype "output"))
    )
    (net (code "52") (name "PWM_07") (class "Default")
      (node (ref "Q07") (pin "1") (pinfunction "1_1") (pintype "passive"))
      (node (ref "R_07") (pin "P$1") (pinfunction "1_P$1") (pintype "passive"))
      (node (ref "TLC_OUTS_1") (pin "7") (pinfunction "7_7") (pintype "passive"))
      (node (ref "TLC_OUTS_2") (pin "7") (pinfunction "7_7") (pintype "passive"))
      (node (ref "U1") (pin "6") (pinfunction "OUT6_6") (pintype "output"))
    )
    (net (code "53") (name "PWM_08") (class "Default")
      (node (ref "Q08") (pin "1") (pinfunction "1_1") (pintype "passive"))
      (node (ref "R_08") (pin "P$1") (pinfunction "1_P$1") (pintype "passive"))
      (node (ref "TLC_OUTS_1") (pin "8") (pinfunction "8_8") (pintype "passive"))
      (node (ref "TLC_OUTS_2") (pin "8") (pinfunction "8_8") (pintype "passive"))
      (node (ref "U1") (pin "7") (pinfunction "OUT7_7") (pintype "output"))
    )
    (net (code "54") (name "PWM_09") (class "Default")
      (node (ref "Q09") (pin "1") (pinfunction "1_1") (pintype "passive"))
      (node (ref "R_09") (pin "P$1") (pinfunction "1_P$1") (pintype "passive"))
      (node (ref "TLC_OUTS_1") (pin "9") (pinfunction "9_9") (pintype "passive"))
      (node (ref "TLC_OUTS_2") (pin "9") (pinfunction "9_9") (pintype "passive"))
      (node (ref "U1") (pin "8") (pinfunction "OUT8_8") (pintype "output"))
    )
    (net (code "55") (name "PWM_10") (class "Default")
      (node (ref "Q10") (pin "1") (pinfunction "1_1") (pintype "passive"))
      (node (ref "R_10") (pin "P$1") (pinfunction "1_P$1") (pintype "passive"))
      (node (ref "TLC_OUTS_1") (pin "10") (pinfunction "10_10") (pintype "passive"))
      (node (ref "TLC_OUTS_2") (pin "10") (pinfunction "10_10") (pintype "passive"))
      (node (ref "U1") (pin "9") (pinfunction "OUT9_9") (pintype "output"))
    )
    (net (code "56") (name "PWM_11") (class "Default")
      (node (ref "Q11") (pin "1") (pinfunction "1_1") (pintype "passive"))
      (node (ref "R_11") (pin "P$1") (pinfunction "1_P$1") (pintype "passive"))
      (node (ref "TLC_OUTS_1") (pin "11") (pinfunction "11_11") (pintype "passive"))
      (node (ref "TLC_OUTS_2") (pin "11") (pinfunction "11_11") (pintype "passive"))
      (node (ref "U1") (pin "10") (pinfunction "OUT10_10") (pintype "output"))
    )
    (net (code "57") (name "PWM_12") (class "Default")
      (node (ref "Q12") (pin "1") (pinfunction "1_1") (pintype "passive"))
      (node (ref "R_12") (pin "P$1") (pinfunction "1_P$1") (pintype "passive"))
      (node (ref "TLC_OUTS_1") (pin "12") (pinfunction "12_12") (pintype "passive"))
      (node (ref "TLC_OUTS_2") (pin "12") (pinfunction "12_12") (pintype "passive"))
      (node (ref "U1") (pin "11") (pinfunction "OUT11_11") (pintype "output"))
    )
    (net (code "58") (name "PWM_13") (class "Default")
      (node (ref "Q13") (pin "1") (pinfunction "1_1") (pintype "passive"))
      (node (ref "R_13") (pin "P$1") (pinfunction "1_P$1") (pintype "passive"))
      (node (ref "TLC_OUTS_1") (pin "13") (pinfunction "13_13") (pintype "passive"))
      (node (ref "TLC_OUTS_2") (pin "13") (pinfunction "13_13") (pintype "passive"))
      (node (ref "U1") (pin "12") (pinfunction "OUT12_12") (pintype "output"))
    )
    (net (code "59") (name "PWM_14") (class "Default")
      (node (ref "Q14") (pin "1") (pinfunction "1_1") (pintype "passive"))
      (node (ref "R_14") (pin "P$1") (pinfunction "1_P$1") (pintype "passive"))
      (node (ref "TLC_OUTS_1") (pin "14") (pinfunction "14_14") (pintype "passive"))
      (node (ref "TLC_OUTS_2") (pin "14") (pinfunction "14_14") (pintype "passive"))
      (node (ref "U1") (pin "13") (pinfunction "OUT13_13") (pintype "output"))
    )
    (net (code "60") (name "PWM_15") (class "Default")
      (node (ref "Q15") (pin "1") (pinfunction "1_1") (pintype "passive"))
      (node (ref "R_15") (pin "P$1") (pinfunction "1_P$1") (pintype "passive"))
      (node (ref "TLC_OUTS_1") (pin "15") (pinfunction "15_15") (pintype "passive"))
      (node (ref "TLC_OUTS_2") (pin "15") (pinfunction "15_15") (pintype "passive"))
      (node (ref "U1") (pin "14") (pinfunction "OUT14_14") (pintype "output"))
    )
    (net (code "61") (name "PWM_16") (class "Default")
      (node (ref "Q16") (pin "1") (pinfunction "1_1") (pintype "passive"))
      (node (ref "R_16") (pin "P$1") (pinfunction "1_P$1") (pintype "passive"))
      (node (ref "TLC_OUTS_1") (pin "16") (pinfunction "16_16") (pintype "passive"))
      (node (ref "TLC_OUTS_2") (pin "16") (pinfunction "16_16") (pintype "passive"))
      (node (ref "U1") (pin "15") (pinfunction "OUT15_15") (pintype "output"))
    )
    (net (code "62") (name "PWM_17") (class "Default")
      (node (ref "NANO_PINS_1") (pin "8") (pinfunction "8_8") (pintype "passive"))
      (node (ref "NANO_PINS_2") (pin "8") (pinfunction "8_8") (pintype "passive"))
      (node (ref "Q17") (pin "1") (pinfunction "1_1") (pintype "passive"))
      (node (ref "U$1") (pin "D5") (pinfunction "D5_D5") (pintype "bidirectional"))
    )
    (net (code "63") (name "PWM_18") (class "Default")
      (node (ref "NANO_PINS_1") (pin "9") (pinfunction "9_9") (pintype "passive"))
      (node (ref "NANO_PINS_2") (pin "9") (pinfunction "9_9") (pintype "passive"))
      (node (ref "Q18") (pin "1") (pinfunction "1_1") (pintype "passive"))
      (node (ref "U$1") (pin "D6") (pinfunction "D6_D6") (pintype "bidirectional"))
    )
    (net (code "64") (name "S_CLK") (class "Default")
      (node (ref "CHAIN_IN_1") (pin "5") (pinfunction "5_5") (pintype "passive"))
      (node (ref "CHAIN_IN_2") (pin "5") (pinfunction "5_5") (pintype "passive"))
      (node (ref "CHAIN_OUT_1") (pin "5") (pinfunction "5_5") (pintype "passive"))
      (node (ref "CHAIN_OUT_2") (pin "5") (pinfunction "5_5") (pintype "passive"))
      (node (ref "CHAIN_OUT_3") (pin "5") (pinfunction "5_5") (pintype "passive"))
      (node (ref "CHIAN_IN_2") (pin "5") (pinfunction "5_5") (pintype "passive"))
      (node (ref "NANO_PWRS_1") (pin "15") (pinfunction "15_15") (pintype "passive"))
      (node (ref "NANO_PWRS_2") (pin "15") (pinfunction "15_15") (pintype "passive"))
      (node (ref "U$1") (pin "D13") (pinfunction "D13_D13") (pintype "bidirectional"))
      (node (ref "U1") (pin "25") (pinfunction "SCLK_25") (pintype "input"))
    )
    (net (code "65") (name "S_IN") (class "Default")
      (node (ref "CHAIN_IN_1") (pin "4") (pinfunction "4_4") (pintype "passive"))
      (node (ref "CHAIN_IN_2") (pin "4") (pinfunction "4_4") (pintype "passive"))
      (node (ref "CHIAN_IN_2") (pin "4") (pinfunction "4_4") (pintype "passive"))
      (node (ref "NANO_PINS_1") (pin "14") (pinfunction "14_14") (pintype "passive"))
      (node (ref "NANO_PINS_2") (pin "14") (pinfunction "14_14") (pintype "passive"))
      (node (ref "U$1") (pin "D11") (pinfunction "D11_D11") (pintype "bidirectional"))
      (node (ref "U1") (pin "26") (pinfunction "SIN_26") (pintype "input"))
    )
    (net (code "66") (name "S_OUT") (class "Default")
      (node (ref "CHAIN_OUT_1") (pin "4") (pinfunction "4_4") (pintype "passive"))
      (node (ref "CHAIN_OUT_2") (pin "4") (pinfunction "4_4") (pintype "passive"))
      (node (ref "CHAIN_OUT_3") (pin "4") (pinfunction "4_4") (pintype "passive"))
      (node (ref "U1") (pin "17") (pinfunction "SOUT_17") (pintype "output"))
    )
    (net (code "67") (name "XLAT") (class "Default")
      (node (ref "CHAIN_IN_1") (pin "7") (pinfunction "7_7") (pintype "passive"))
      (node (ref "CHAIN_IN_2") (pin "7") (pinfunction "7_7") (pintype "passive"))
      (node (ref "CHAIN_OUT_1") (pin "7") (pinfunction "7_7") (pintype "passive"))
      (node (ref "CHAIN_OUT_2") (pin "7") (pinfunction "7_7") (pintype "passive"))
      (node (ref "CHAIN_OUT_3") (pin "7") (pinfunction "7_7") (pintype "passive"))
      (node (ref "CHIAN_IN_2") (pin "7") (pinfunction "7_7") (pintype "passive"))
      (node (ref "NANO_PINS_1") (pin "12") (pinfunction "12_12") (pintype "passive"))
      (node (ref "NANO_PINS_2") (pin "12") (pinfunction "12_12") (pintype "passive"))
      (node (ref "U$1") (pin "D9") (pinfunction "D9_D9") (pintype "bidirectional"))
      (node (ref "U1") (pin "24") (pinfunction "XLAT_24") (pintype "input"))
    )
    (net (code "68") (name "unconnected-(U$1-PadICSP1)") (class "Default")
      (node (ref "U$1") (pin "ICSP1") (pinfunction "ICSP1_ICSP1") (pintype "bidirectional"))
    )
    (net (code "69") (name "unconnected-(U$1-PadICSP2)") (class "Default")
      (node (ref "U$1") (pin "ICSP2") (pinfunction "ICSP2_ICSP2") (pintype "bidirectional"))
    )
    (net (code "70") (name "unconnected-(U$1-PadICSP3)") (class "Default")
      (node (ref "U$1") (pin "ICSP3") (pinfunction "ICSP3_ICSP3") (pintype "bidirectional"))
    )
    (net (code "71") (name "unconnected-(U$1-PadICSP4)") (class "Default")
      (node (ref "U$1") (pin "ICSP4") (pinfunction "ICSP4_ICSP4") (pintype "bidirectional"))
    )
    (net (code "72") (name "unconnected-(U$1-PadICSP5)") (class "Default")
      (node (ref "U$1") (pin "ICSP5") (pinfunction "ICSP5_ICSP5") (pintype "bidirectional"))
    )
    (net (code "73") (name "unconnected-(U$1-PadICSP6)") (class "Default")
      (node (ref "U$1") (pin "ICSP6") (pinfunction "ICSP6_ICSP6") (pintype "bidirectional"))
    )
    (net (code "74") (name "unconnected-(U1-XERR-Pad16)") (class "Default")
      (node (ref "U1") (pin "16") (pinfunction "XERR_16") (pintype "output"))
    )
  )
)
